# 06_KEY.net
KiCad netlist of a schematic drawn in Altium Designer
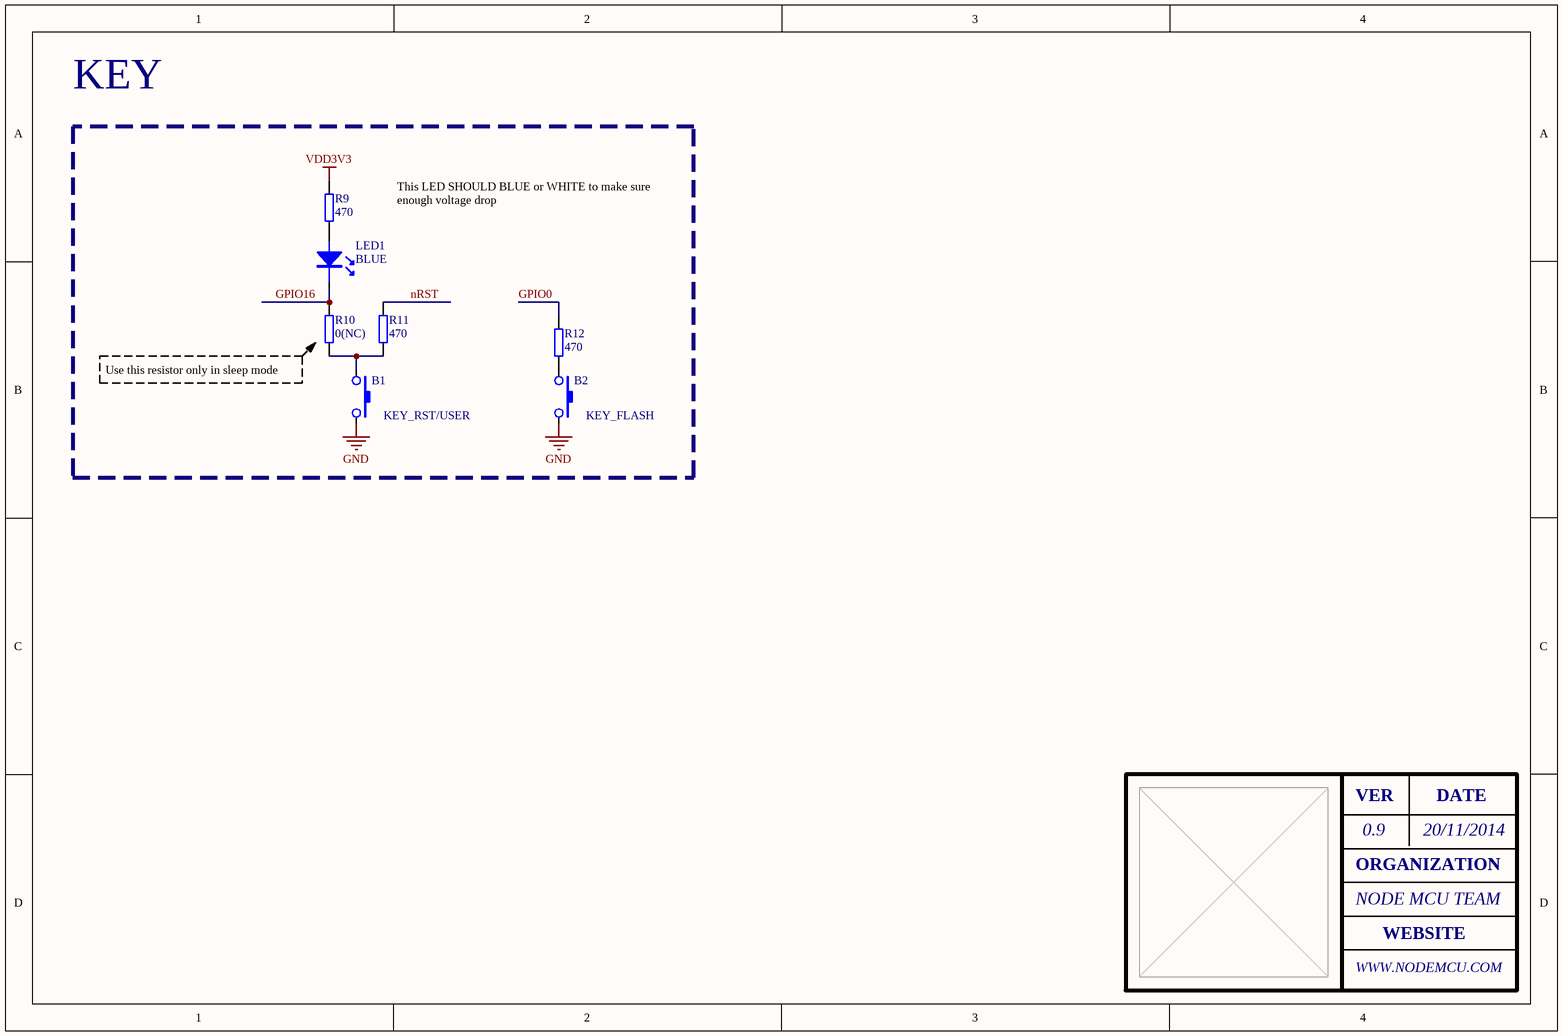
[diagram p0: 06_KEY.SchDoc]

(export (version "E")
  (design (tool "Eeschema 10.0.6"))
  (components
    (comp (ref "B1")
      (value "KEY_RST/USER")
      (footprint "SMT_SW_PTS_820")
      (description "SMT Tactile ‎Switch PTS 820 Series")
      (libsource (lib "cupmat") (part "SMT_SW_PTS_820"))
    )
    (comp (ref "B2")
      (value "KEY_FLASH")
      (footprint "SMT_SW_PTS_820")
      (description "SMT Tactile ‎Switch PTS 820 Series")
      (libsource (lib "cupmat") (part "SMT_SW_PTS_820"))
    )
    (comp (ref "LED1")
      (value "BLUE")
      (footprint "SMT_LED_0603")
      (description "SMT LED")
      (libsource (lib "cupmat") (part "SMT_LED_0603"))
    )
    (comp (ref "R9")
      (value "470")
      (footprint "SMT_R_0402")
      (description "Surface mount resistor 0402")
      (libsource (lib "cupmat") (part "SMT_R_0402"))
    )
    (comp (ref "R10")
      (value "0(NC)")
      (footprint "SMT_R_0402")
      (description "Surface mount resistor 0402")
      (libsource (lib "cupmat") (part "SMT_R_0402"))
    )
    (comp (ref "R11")
      (value "470")
      (footprint "SMT_R_0402")
      (description "Surface mount resistor 0402")
      (libsource (lib "cupmat") (part "SMT_R_0402"))
    )
    (comp (ref "R12")
      (value "470")
      (footprint "SMT_R_0402")
      (description "Surface mount resistor 0402")
      (libsource (lib "cupmat") (part "SMT_R_0402"))
    )
  )
  (nets
    (net (code "1") (name "/GPIO0") (class "Default")
      (node (ref "R12") (pin "2") (pinfunction "2_2") (pintype "passive"))
    )
    (net (code "2") (name "/GPIO16") (class "Default")
      (node (ref "LED1") (pin "2") (pinfunction "K_2") (pintype "passive"))
      (node (ref "R10") (pin "2") (pinfunction "2_2") (pintype "passive"))
    )
    (net (code "3") (name "/nRST") (class "Default")
      (node (ref "R11") (pin "2") (pinfunction "2_2") (pintype "passive"))
    )
    (net (code "4") (name "GND") (class "Default")
      (node (ref "B1") (pin "2") (pinfunction "2_2") (pintype "passive"))
      (node (ref "B2") (pin "2") (pinfunction "2_2") (pintype "passive"))
    )
    (net (code "5") (name "Net-(B1-Pad1)") (class "Default")
      (node (ref "B1") (pin "1") (pinfunction "1_1") (pintype "passive"))
      (node (ref "R10") (pin "1") (pinfunction "1_1") (pintype "passive"))
      (node (ref "R11") (pin "1") (pinfunction "1_1") (pintype "passive"))
    )
    (net (code "6") (name "Net-(B2-Pad1)") (class "Default")
      (node (ref "B2") (pin "1") (pinfunction "1_1") (pintype "passive"))
      (node (ref "R12") (pin "1") (pinfunction "1_1") (pintype "passive"))
    )
    (net (code "7") (name "Net-(LED1-A)") (class "Default")
      (node (ref "LED1") (pin "1") (pinfunction "A_1") (pintype "passive"))
      (node (ref "R9") (pin "1") (pinfunction "1_1") (pintype "passive"))
    )
    (net (code "8") (name "VDD3V3") (class "Default")
      (node (ref "R9") (pin "2") (pinfunction "2_2") (pintype "passive"))
    )
  )
)
